# analog.net
KiCad netlist of a schematic drawn in Altium Designer
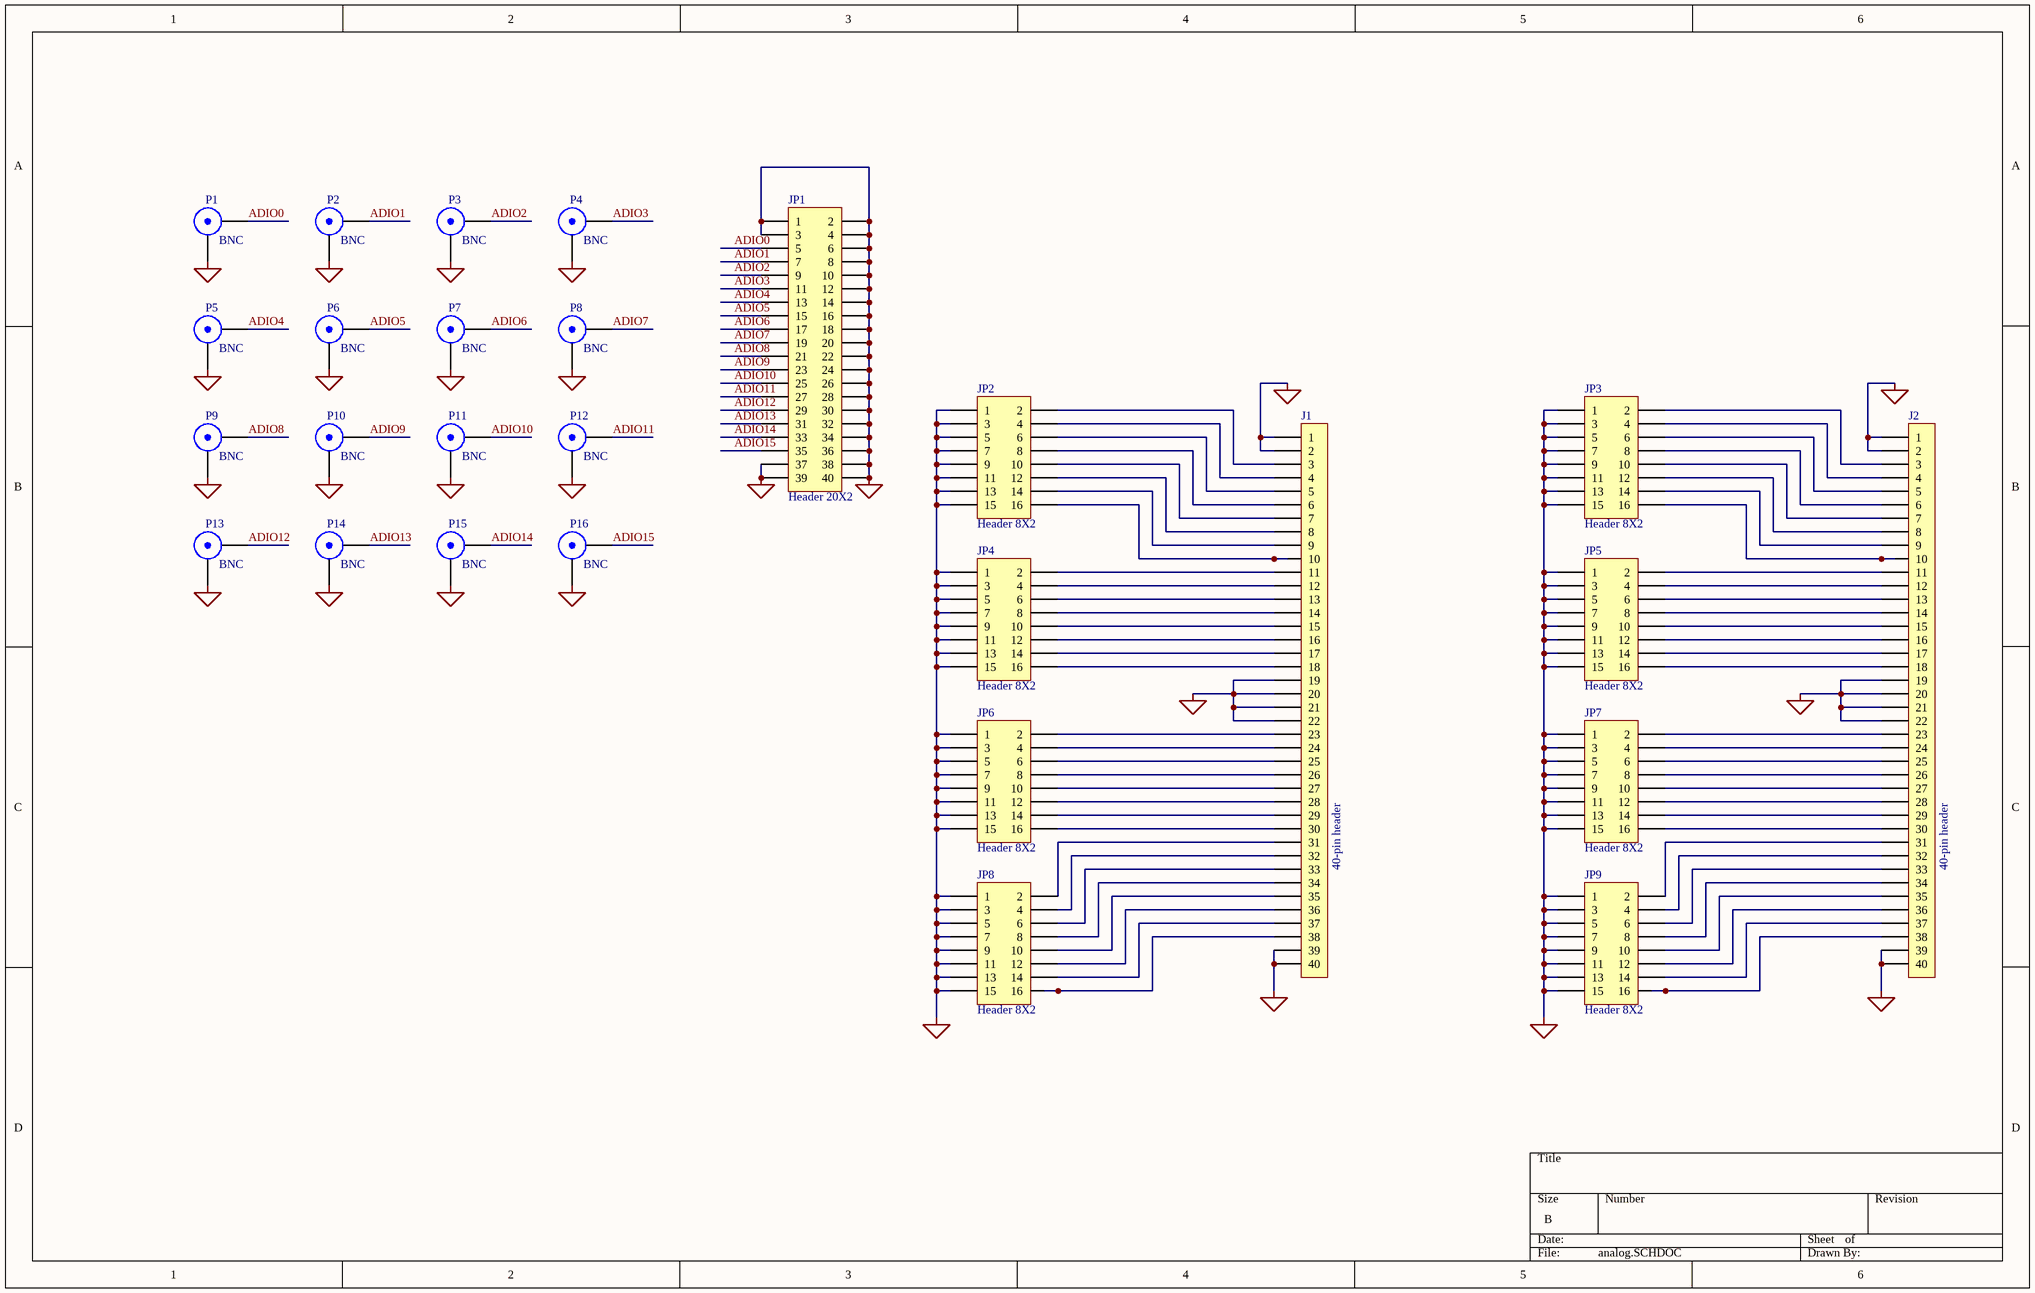
[diagram p0: analog.SCHDOC]

(export (version "E")
  (design (tool "Eeschema 10.0.6"))
  (components
    (comp (ref "J1")
      (value "40-pin header")
      (footprint "HDR2X20")
      (description "Simple 40pin connector")
      (libsource (lib "My devices") (part "40PINHEADER"))
    )
    (comp (ref "J2")
      (value "40-pin header")
      (footprint "HDR2X20")
      (description "Simple 40pin connector")
      (libsource (lib "My devices") (part "40PINHEADER"))
    )
    (comp (ref "JP1")
      (value "Header 20X2")
      (footprint "HDR2X20")
      (description "Header, 20-Pin, Dual row")
      (fields (field (name "MANUFACTURER") "Generic Components") (field (name "PUBLISHER") "Altium Limited"))
      (libsource (lib "Miscellaneous Connectors") (part "Header 20X2"))
    )
    (comp (ref "JP2")
      (value "Header 8X2")
      (footprint "HDR2X8")
      (description "Header, 8-Pin, Dual row")
      (fields (field (name "MANUFACTURER") "Generic Components") (field (name "PUBLISHER") "Altium Limited"))
      (libsource (lib "Miscellaneous Connectors") (part "Header 8X2"))
    )
    (comp (ref "JP3")
      (value "Header 8X2")
      (footprint "HDR2X8")
      (description "Header, 8-Pin, Dual row")
      (fields (field (name "MANUFACTURER") "Generic Components") (field (name "PUBLISHER") "Altium Limited"))
      (libsource (lib "Miscellaneous Connectors") (part "Header 8X2"))
    )
    (comp (ref "JP4")
      (value "Header 8X2")
      (footprint "HDR2X8")
      (description "Header, 8-Pin, Dual row")
      (fields (field (name "MANUFACTURER") "Generic Components") (field (name "PUBLISHER") "Altium Limited"))
      (libsource (lib "Miscellaneous Connectors") (part "Header 8X2"))
    )
    (comp (ref "JP5")
      (value "Header 8X2")
      (footprint "HDR2X8")
      (description "Header, 8-Pin, Dual row")
      (fields (field (name "MANUFACTURER") "Generic Components") (field (name "PUBLISHER") "Altium Limited"))
      (libsource (lib "Miscellaneous Connectors") (part "Header 8X2"))
    )
    (comp (ref "JP6")
      (value "Header 8X2")
      (footprint "HDR2X8")
      (description "Header, 8-Pin, Dual row")
      (fields (field (name "MANUFACTURER") "Generic Components") (field (name "PUBLISHER") "Altium Limited"))
      (libsource (lib "Miscellaneous Connectors") (part "Header 8X2"))
    )
    (comp (ref "JP7")
      (value "Header 8X2")
      (footprint "HDR2X8")
      (description "Header, 8-Pin, Dual row")
      (fields (field (name "MANUFACTURER") "Generic Components") (field (name "PUBLISHER") "Altium Limited"))
      (libsource (lib "Miscellaneous Connectors") (part "Header 8X2"))
    )
    (comp (ref "JP8")
      (value "Header 8X2")
      (footprint "HDR2X8")
      (description "Header, 8-Pin, Dual row")
      (fields (field (name "MANUFACTURER") "Generic Components") (field (name "PUBLISHER") "Altium Limited"))
      (libsource (lib "Miscellaneous Connectors") (part "Header 8X2"))
    )
    (comp (ref "JP9")
      (value "Header 8X2")
      (footprint "HDR2X8")
      (description "Header, 8-Pin, Dual row")
      (fields (field (name "MANUFACTURER") "Generic Components") (field (name "PUBLISHER") "Altium Limited"))
      (libsource (lib "Miscellaneous Connectors") (part "Header 8X2"))
    )
    (comp (ref "P1")
      (value "BNC")
      (footprint "Vertical BNC 227699-1")
      (description "BNC Elbow Connector")
      (fields (field (name "MANUFACTURER") "Generic Components") (field (name "PUBLISHER") "Altium Limited"))
      (libsource (lib "Miscellaneous Connectors") (part "BNC"))
    )
    (comp (ref "P2")
      (value "BNC")
      (footprint "Vertical BNC 227699-1")
      (description "BNC Elbow Connector")
      (fields (field (name "MANUFACTURER") "Generic Components") (field (name "PUBLISHER") "Altium Limited"))
      (libsource (lib "Miscellaneous Connectors") (part "BNC"))
    )
    (comp (ref "P3")
      (value "BNC")
      (footprint "Vertical BNC 227699-1")
      (description "BNC Elbow Connector")
      (fields (field (name "MANUFACTURER") "Generic Components") (field (name "PUBLISHER") "Altium Limited"))
      (libsource (lib "Miscellaneous Connectors") (part "BNC"))
    )
    (comp (ref "P4")
      (value "BNC")
      (footprint "Vertical BNC 227699-1")
      (description "BNC Elbow Connector")
      (fields (field (name "MANUFACTURER") "Generic Components") (field (name "PUBLISHER") "Altium Limited"))
      (libsource (lib "Miscellaneous Connectors") (part "BNC"))
    )
    (comp (ref "P5")
      (value "BNC")
      (footprint "Vertical BNC 227699-1")
      (description "BNC Elbow Connector")
      (fields (field (name "MANUFACTURER") "Generic Components") (field (name "PUBLISHER") "Altium Limited"))
      (libsource (lib "Miscellaneous Connectors") (part "BNC"))
    )
    (comp (ref "P6")
      (value "BNC")
      (footprint "Vertical BNC 227699-1")
      (description "BNC Elbow Connector")
      (fields (field (name "MANUFACTURER") "Generic Components") (field (name "PUBLISHER") "Altium Limited"))
      (libsource (lib "Miscellaneous Connectors") (part "BNC"))
    )
    (comp (ref "P7")
      (value "BNC")
      (footprint "Vertical BNC 227699-1")
      (description "BNC Elbow Connector")
      (fields (field (name "MANUFACTURER") "Generic Components") (field (name "PUBLISHER") "Altium Limited"))
      (libsource (lib "Miscellaneous Connectors") (part "BNC"))
    )
    (comp (ref "P8")
      (value "BNC")
      (footprint "Vertical BNC 227699-1")
      (description "BNC Elbow Connector")
      (fields (field (name "MANUFACTURER") "Generic Components") (field (name "PUBLISHER") "Altium Limited"))
      (libsource (lib "Miscellaneous Connectors") (part "BNC"))
    )
    (comp (ref "P9")
      (value "BNC")
      (footprint "Vertical BNC 227699-1")
      (description "BNC Elbow Connector")
      (fields (field (name "MANUFACTURER") "Generic Components") (field (name "PUBLISHER") "Altium Limited"))
      (libsource (lib "Miscellaneous Connectors") (part "BNC"))
    )
    (comp (ref "P10")
      (value "BNC")
      (footprint "Vertical BNC 227699-1")
      (description "BNC Elbow Connector")
      (fields (field (name "MANUFACTURER") "Generic Components") (field (name "PUBLISHER") "Altium Limited"))
      (libsource (lib "Miscellaneous Connectors") (part "BNC"))
    )
    (comp (ref "P11")
      (value "BNC")
      (footprint "Vertical BNC 227699-1")
      (description "BNC Elbow Connector")
      (fields (field (name "MANUFACTURER") "Generic Components") (field (name "PUBLISHER") "Altium Limited"))
      (libsource (lib "Miscellaneous Connectors") (part "BNC"))
    )
    (comp (ref "P12")
      (value "BNC")
      (footprint "Vertical BNC 227699-1")
      (description "BNC Elbow Connector")
      (fields (field (name "MANUFACTURER") "Generic Components") (field (name "PUBLISHER") "Altium Limited"))
      (libsource (lib "Miscellaneous Connectors") (part "BNC"))
    )
    (comp (ref "P13")
      (value "BNC")
      (footprint "Vertical BNC 227699-1")
      (description "BNC Elbow Connector")
      (fields (field (name "MANUFACTURER") "Generic Components") (field (name "PUBLISHER") "Altium Limited"))
      (libsource (lib "Miscellaneous Connectors") (part "BNC"))
    )
    (comp (ref "P14")
      (value "BNC")
      (footprint "Vertical BNC 227699-1")
      (description "BNC Elbow Connector")
      (fields (field (name "MANUFACTURER") "Generic Components") (field (name "PUBLISHER") "Altium Limited"))
      (libsource (lib "Miscellaneous Connectors") (part "BNC"))
    )
    (comp (ref "P15")
      (value "BNC")
      (footprint "Vertical BNC 227699-1")
      (description "BNC Elbow Connector")
      (fields (field (name "MANUFACTURER") "Generic Components") (field (name "PUBLISHER") "Altium Limited"))
      (libsource (lib "Miscellaneous Connectors") (part "BNC"))
    )
    (comp (ref "P16")
      (value "BNC")
      (footprint "Vertical BNC 227699-1")
      (description "BNC Elbow Connector")
      (fields (field (name "MANUFACTURER") "Generic Components") (field (name "PUBLISHER") "Altium Limited"))
      (libsource (lib "Miscellaneous Connectors") (part "BNC"))
    )
  )
  (nets
    (net (code "1") (name "/ADIO0") (class "Default")
      (node (ref "JP1") (pin "5") (pinfunction "5_5") (pintype "passive"))
      (node (ref "P1") (pin "1") (pinfunction "X_1") (pintype "passive"))
    )
    (net (code "2") (name "/ADIO1") (class "Default")
      (node (ref "JP1") (pin "7") (pinfunction "7_7") (pintype "passive"))
      (node (ref "P2") (pin "1") (pinfunction "X_1") (pintype "passive"))
    )
    (net (code "3") (name "/ADIO2") (class "Default")
      (node (ref "JP1") (pin "9") (pinfunction "9_9") (pintype "passive"))
      (node (ref "P3") (pin "1") (pinfunction "X_1") (pintype "passive"))
    )
    (net (code "4") (name "/ADIO3") (class "Default")
      (node (ref "JP1") (pin "11") (pinfunction "11_11") (pintype "passive"))
      (node (ref "P4") (pin "1") (pinfunction "X_1") (pintype "passive"))
    )
    (net (code "5") (name "/ADIO4") (class "Default")
      (node (ref "JP1") (pin "13") (pinfunction "13_13") (pintype "passive"))
      (node (ref "P5") (pin "1") (pinfunction "X_1") (pintype "passive"))
    )
    (net (code "6") (name "/ADIO5") (class "Default")
      (node (ref "JP1") (pin "15") (pinfunction "15_15") (pintype "passive"))
      (node (ref "P6") (pin "1") (pinfunction "X_1") (pintype "passive"))
    )
    (net (code "7") (name "/ADIO6") (class "Default")
      (node (ref "JP1") (pin "17") (pinfunction "17_17") (pintype "passive"))
      (node (ref "P7") (pin "1") (pinfunction "X_1") (pintype "passive"))
    )
    (net (code "8") (name "/ADIO7") (class "Default")
      (node (ref "JP1") (pin "19") (pinfunction "19_19") (pintype "passive"))
      (node (ref "P8") (pin "1") (pinfunction "X_1") (pintype "passive"))
    )
    (net (code "9") (name "/ADIO8") (class "Default")
      (node (ref "JP1") (pin "21") (pinfunction "21_21") (pintype "passive"))
      (node (ref "P9") (pin "1") (pinfunction "X_1") (pintype "passive"))
    )
    (net (code "10") (name "/ADIO9") (class "Default")
      (node (ref "JP1") (pin "23") (pinfunction "23_23") (pintype "passive"))
      (node (ref "P10") (pin "1") (pinfunction "X_1") (pintype "passive"))
    )
    (net (code "11") (name "/ADIO10") (class "Default")
      (node (ref "JP1") (pin "25") (pinfunction "25_25") (pintype "passive"))
      (node (ref "P11") (pin "1") (pinfunction "X_1") (pintype "passive"))
    )
    (net (code "12") (name "/ADIO11") (class "Default")
      (node (ref "JP1") (pin "27") (pinfunction "27_27") (pintype "passive"))
      (node (ref "P12") (pin "1") (pinfunction "X_1") (pintype "passive"))
    )
    (net (code "13") (name "/ADIO12") (class "Default")
      (node (ref "JP1") (pin "29") (pinfunction "29_29") (pintype "passive"))
      (node (ref "P13") (pin "1") (pinfunction "X_1") (pintype "passive"))
    )
    (net (code "14") (name "/ADIO13") (class "Default")
      (node (ref "JP1") (pin "31") (pinfunction "31_31") (pintype "passive"))
      (node (ref "P14") (pin "1") (pinfunction "X_1") (pintype "passive"))
    )
    (net (code "15") (name "/ADIO14") (class "Default")
      (node (ref "JP1") (pin "33") (pinfunction "33_33") (pintype "passive"))
      (node (ref "P15") (pin "1") (pinfunction "X_1") (pintype "passive"))
    )
    (net (code "16") (name "/ADIO15") (class "Default")
      (node (ref "JP1") (pin "35") (pinfunction "35_35") (pintype "passive"))
      (node (ref "P16") (pin "1") (pinfunction "X_1") (pintype "passive"))
    )
    (net (code "17") (name "AGND") (class "Default")
      (node (ref "JP1") (pin "1") (pinfunction "1_1") (pintype "passive"))
      (node (ref "JP1") (pin "10") (pinfunction "10_10") (pintype "passive"))
      (node (ref "JP1") (pin "12") (pinfunction "12_12") (pintype "passive"))
      (node (ref "JP1") (pin "14") (pinfunction "14_14") (pintype "passive"))
      (node (ref "JP1") (pin "16") (pinfunction "16_16") (pintype "passive"))
      (node (ref "JP1") (pin "18") (pinfunction "18_18") (pintype "passive"))
      (node (ref "JP1") (pin "2") (pinfunction "2_2") (pintype "passive"))
      (node (ref "JP1") (pin "20") (pinfunction "20_20") (pintype "passive"))
      (node (ref "JP1") (pin "22") (pinfunction "22_22") (pintype "passive"))
      (node (ref "JP1") (pin "24") (pinfunction "24_24") (pintype "passive"))
      (node (ref "JP1") (pin "26") (pinfunction "26_26") (pintype "passive"))
      (node (ref "JP1") (pin "28") (pinfunction "28_28") (pintype "passive"))
      (node (ref "JP1") (pin "3") (pinfunction "3_3") (pintype "passive"))
      (node (ref "JP1") (pin "30") (pinfunction "30_30") (pintype "passive"))
      (node (ref "JP1") (pin "32") (pinfunction "32_32") (pintype "passive"))
      (node (ref "JP1") (pin "34") (pinfunction "34_34") (pintype "passive"))
      (node (ref "JP1") (pin "36") (pinfunction "36_36") (pintype "passive"))
      (node (ref "JP1") (pin "37") (pinfunction "37_37") (pintype "passive"))
      (node (ref "JP1") (pin "38") (pinfunction "38_38") (pintype "passive"))
      (node (ref "JP1") (pin "39") (pinfunction "39_39") (pintype "passive"))
      (node (ref "JP1") (pin "4") (pinfunction "4_4") (pintype "passive"))
      (node (ref "JP1") (pin "40") (pinfunction "40_40") (pintype "passive"))
      (node (ref "JP1") (pin "6") (pinfunction "6_6") (pintype "passive"))
      (node (ref "JP1") (pin "8") (pinfunction "8_8") (pintype "passive"))
      (node (ref "P1") (pin "2") (pinfunction "Y_2") (pintype "passive"))
      (node (ref "P10") (pin "2") (pinfunction "Y_2") (pintype "passive"))
      (node (ref "P11") (pin "2") (pinfunction "Y_2") (pintype "passive"))
      (node (ref "P12") (pin "2") (pinfunction "Y_2") (pintype "passive"))
      (node (ref "P13") (pin "2") (pinfunction "Y_2") (pintype "passive"))
      (node (ref "P14") (pin "2") (pinfunction "Y_2") (pintype "passive"))
      (node (ref "P15") (pin "2") (pinfunction "Y_2") (pintype "passive"))
      (node (ref "P16") (pin "2") (pinfunction "Y_2") (pintype "passive"))
      (node (ref "P2") (pin "2") (pinfunction "Y_2") (pintype "passive"))
      (node (ref "P3") (pin "2") (pinfunction "Y_2") (pintype "passive"))
      (node (ref "P4") (pin "2") (pinfunction "Y_2") (pintype "passive"))
      (node (ref "P5") (pin "2") (pinfunction "Y_2") (pintype "passive"))
      (node (ref "P6") (pin "2") (pinfunction "Y_2") (pintype "passive"))
      (node (ref "P7") (pin "2") (pinfunction "Y_2") (pintype "passive"))
      (node (ref "P8") (pin "2") (pinfunction "Y_2") (pintype "passive"))
      (node (ref "P9") (pin "2") (pinfunction "Y_2") (pintype "passive"))
    )
    (net (code "18") (name "DGND") (class "Default")
      (node (ref "J1") (pin "1") (pinfunction "1_1") (pintype "passive"))
      (node (ref "J1") (pin "19") (pinfunction "19_19") (pintype "passive"))
      (node (ref "J1") (pin "2") (pinfunction "2_2") (pintype "passive"))
      (node (ref "J1") (pin "20") (pinfunction "20_20") (pintype "passive"))
      (node (ref "J1") (pin "21") (pinfunction "21_21") (pintype "passive"))
      (node (ref "J1") (pin "22") (pinfunction "22_22") (pintype "passive"))
      (node (ref "J1") (pin "39") (pinfunction "39_39") (pintype "passive"))
      (node (ref "J1") (pin "40") (pinfunction "40_40") (pintype "passive"))
      (node (ref "J2") (pin "1") (pinfunction "1_1") (pintype "passive"))
      (node (ref "J2") (pin "19") (pinfunction "19_19") (pintype "passive"))
      (node (ref "J2") (pin "2") (pinfunction "2_2") (pintype "passive"))
      (node (ref "J2") (pin "20") (pinfunction "20_20") (pintype "passive"))
      (node (ref "J2") (pin "21") (pinfunction "21_21") (pintype "passive"))
      (node (ref "J2") (pin "22") (pinfunction "22_22") (pintype "passive"))
      (node (ref "J2") (pin "39") (pinfunction "39_39") (pintype "passive"))
      (node (ref "J2") (pin "40") (pinfunction "40_40") (pintype "passive"))
      (node (ref "JP2") (pin "1") (pinfunction "1_1") (pintype "passive"))
      (node (ref "JP2") (pin "11") (pinfunction "11_11") (pintype "passive"))
      (node (ref "JP2") (pin "13") (pinfunction "13_13") (pintype "passive"))
      (node (ref "JP2") (pin "15") (pinfunction "15_15") (pintype "passive"))
      (node (ref "JP2") (pin "3") (pinfunction "3_3") (pintype "passive"))
      (node (ref "JP2") (pin "5") (pinfunction "5_5") (pintype "passive"))
      (node (ref "JP2") (pin "7") (pinfunction "7_7") (pintype "passive"))
      (node (ref "JP2") (pin "9") (pinfunction "9_9") (pintype "passive"))
      (node (ref "JP3") (pin "1") (pinfunction "1_1") (pintype "passive"))
      (node (ref "JP3") (pin "11") (pinfunction "11_11") (pintype "passive"))
      (node (ref "JP3") (pin "13") (pinfunction "13_13") (pintype "passive"))
      (node (ref "JP3") (pin "15") (pinfunction "15_15") (pintype "passive"))
      (node (ref "JP3") (pin "3") (pinfunction "3_3") (pintype "passive"))
      (node (ref "JP3") (pin "5") (pinfunction "5_5") (pintype "passive"))
      (node (ref "JP3") (pin "7") (pinfunction "7_7") (pintype "passive"))
      (node (ref "JP3") (pin "9") (pinfunction "9_9") (pintype "passive"))
      (node (ref "JP4") (pin "1") (pinfunction "1_1") (pintype "passive"))
      (node (ref "JP4") (pin "11") (pinfunction "11_11") (pintype "passive"))
      (node (ref "JP4") (pin "13") (pinfunction "13_13") (pintype "passive"))
      (node (ref "JP4") (pin "15") (pinfunction "15_15") (pintype "passive"))
      (node (ref "JP4") (pin "3") (pinfunction "3_3") (pintype "passive"))
      (node (ref "JP4") (pin "5") (pinfunction "5_5") (pintype "passive"))
      (node (ref "JP4") (pin "7") (pinfunction "7_7") (pintype "passive"))
      (node (ref "JP4") (pin "9") (pinfunction "9_9") (pintype "passive"))
      (node (ref "JP5") (pin "1") (pinfunction "1_1") (pintype "passive"))
      (node (ref "JP5") (pin "11") (pinfunction "11_11") (pintype "passive"))
      (node (ref "JP5") (pin "13") (pinfunction "13_13") (pintype "passive"))
      (node (ref "JP5") (pin "15") (pinfunction "15_15") (pintype "passive"))
      (node (ref "JP5") (pin "3") (pinfunction "3_3") (pintype "passive"))
      (node (ref "JP5") (pin "5") (pinfunction "5_5") (pintype "passive"))
      (node (ref "JP5") (pin "7") (pinfunction "7_7") (pintype "passive"))
      (node (ref "JP5") (pin "9") (pinfunction "9_9") (pintype "passive"))
      (node (ref "JP6") (pin "1") (pinfunction "1_1") (pintype "passive"))
      (node (ref "JP6") (pin "11") (pinfunction "11_11") (pintype "passive"))
      (node (ref "JP6") (pin "13") (pinfunction "13_13") (pintype "passive"))
      (node (ref "JP6") (pin "15") (pinfunction "15_15") (pintype "passive"))
      (node (ref "JP6") (pin "3") (pinfunction "3_3") (pintype "passive"))
      (node (ref "JP6") (pin "5") (pinfunction "5_5") (pintype "passive"))
      (node (ref "JP6") (pin "7") (pinfunction "7_7") (pintype "passive"))
      (node (ref "JP6") (pin "9") (pinfunction "9_9") (pintype "passive"))
      (node (ref "JP7") (pin "1") (pinfunction "1_1") (pintype "passive"))
      (node (ref "JP7") (pin "11") (pinfunction "11_11") (pintype "passive"))
      (node (ref "JP7") (pin "13") (pinfunction "13_13") (pintype "passive"))
      (node (ref "JP7") (pin "15") (pinfunction "15_15") (pintype "passive"))
      (node (ref "JP7") (pin "3") (pinfunction "3_3") (pintype "passive"))
      (node (ref "JP7") (pin "5") (pinfunction "5_5") (pintype "passive"))
      (node (ref "JP7") (pin "7") (pinfunction "7_7") (pintype "passive"))
      (node (ref "JP7") (pin "9") (pinfunction "9_9") (pintype "passive"))
      (node (ref "JP8") (pin "1") (pinfunction "1_1") (pintype "passive"))
      (node (ref "JP8") (pin "11") (pinfunction "11_11") (pintype "passive"))
      (node (ref "JP8") (pin "13") (pinfunction "13_13") (pintype "passive"))
      (node (ref "JP8") (pin "15") (pinfunction "15_15") (pintype "passive"))
      (node (ref "JP8") (pin "3") (pinfunction "3_3") (pintype "passive"))
      (node (ref "JP8") (pin "5") (pinfunction "5_5") (pintype "passive"))
      (node (ref "JP8") (pin "7") (pinfunction "7_7") (pintype "passive"))
      (node (ref "JP8") (pin "9") (pinfunction "9_9") (pintype "passive"))
      (node (ref "JP9") (pin "1") (pinfunction "1_1") (pintype "passive"))
      (node (ref "JP9") (pin "11") (pinfunction "11_11") (pintype "passive"))
      (node (ref "JP9") (pin "13") (pinfunction "13_13") (pintype "passive"))
      (node (ref "JP9") (pin "15") (pinfunction "15_15") (pintype "passive"))
      (node (ref "JP9") (pin "3") (pinfunction "3_3") (pintype "passive"))
      (node (ref "JP9") (pin "5") (pinfunction "5_5") (pintype "passive"))
      (node (ref "JP9") (pin "7") (pinfunction "7_7") (pintype "passive"))
      (node (ref "JP9") (pin "9") (pinfunction "9_9") (pintype "passive"))
    )
    (net (code "19") (name "Net-(J1-Pad3)") (class "Default")
      (node (ref "J1") (pin "3") (pinfunction "3_3") (pintype "passive"))
      (node (ref "JP2") (pin "2") (pinfunction "2_2") (pintype "passive"))
    )
    (net (code "20") (name "Net-(J1-Pad4)") (class "Default")
      (node (ref "J1") (pin "4") (pinfunction "4_4") (pintype "passive"))
      (node (ref "JP2") (pin "4") (pinfunction "4_4") (pintype "passive"))
    )
    (net (code "21") (name "Net-(J1-Pad5)") (class "Default")
      (node (ref "J1") (pin "5") (pinfunction "5_5") (pintype "passive"))
      (node (ref "JP2") (pin "6") (pinfunction "6_6") (pintype "passive"))
    )
    (net (code "22") (name "Net-(J1-Pad6)") (class "Default")
      (node (ref "J1") (pin "6") (pinfunction "6_6") (pintype "passive"))
      (node (ref "JP2") (pin "8") (pinfunction "8_8") (pintype "passive"))
    )
    (net (code "23") (name "Net-(J1-Pad7)") (class "Default")
      (node (ref "J1") (pin "7") (pinfunction "7_7") (pintype "passive"))
      (node (ref "JP2") (pin "10") (pinfunction "10_10") (pintype "passive"))
    )
    (net (code "24") (name "Net-(J1-Pad8)") (class "Default")
      (node (ref "J1") (pin "8") (pinfunction "8_8") (pintype "passive"))
      (node (ref "JP2") (pin "12") (pinfunction "12_12") (pintype "passive"))
    )
    (net (code "25") (name "Net-(J1-Pad9)") (class "Default")
      (node (ref "J1") (pin "9") (pinfunction "9_9") (pintype "passive"))
      (node (ref "JP2") (pin "14") (pinfunction "14_14") (pintype "passive"))
    )
    (net (code "26") (name "Net-(J1-Pad10)") (class "Default")
      (node (ref "J1") (pin "10") (pinfunction "10_10") (pintype "passive"))
      (node (ref "JP2") (pin "16") (pinfunction "16_16") (pintype "passive"))
    )
    (net (code "27") (name "Net-(J1-Pad11)") (class "Default")
      (node (ref "J1") (pin "11") (pinfunction "11_11") (pintype "passive"))
      (node (ref "JP4") (pin "2") (pinfunction "2_2") (pintype "passive"))
    )
    (net (code "28") (name "Net-(J1-Pad12)") (class "Default")
      (node (ref "J1") (pin "12") (pinfunction "12_12") (pintype "passive"))
      (node (ref "JP4") (pin "4") (pinfunction "4_4") (pintype "passive"))
    )
    (net (code "29") (name "Net-(J1-Pad13)") (class "Default")
      (node (ref "J1") (pin "13") (pinfunction "13_13") (pintype "passive"))
      (node (ref "JP4") (pin "6") (pinfunction "6_6") (pintype "passive"))
    )
    (net (code "30") (name "Net-(J1-Pad14)") (class "Default")
      (node (ref "J1") (pin "14") (pinfunction "14_14") (pintype "passive"))
      (node (ref "JP4") (pin "8") (pinfunction "8_8") (pintype "passive"))
    )
    (net (code "31") (name "Net-(J1-Pad15)") (class "Default")
      (node (ref "J1") (pin "15") (pinfunction "15_15") (pintype "passive"))
      (node (ref "JP4") (pin "10") (pinfunction "10_10") (pintype "passive"))
    )
    (net (code "32") (name "Net-(J1-Pad16)") (class "Default")
      (node (ref "J1") (pin "16") (pinfunction "16_16") (pintype "passive"))
      (node (ref "JP4") (pin "12") (pinfunction "12_12") (pintype "passive"))
    )
    (net (code "33") (name "Net-(J1-Pad17)") (class "Default")
      (node (ref "J1") (pin "17") (pinfunction "17_17") (pintype "passive"))
      (node (ref "JP4") (pin "14") (pinfunction "14_14") (pintype "passive"))
    )
    (net (code "34") (name "Net-(J1-Pad18)") (class "Default")
      (node (ref "J1") (pin "18") (pinfunction "18_18") (pintype "passive"))
      (node (ref "JP4") (pin "16") (pinfunction "16_16") (pintype "passive"))
    )
    (net (code "35") (name "Net-(J1-Pad23)") (class "Default")
      (node (ref "J1") (pin "23") (pinfunction "23_23") (pintype "passive"))
      (node (ref "JP6") (pin "2") (pinfunction "2_2") (pintype "passive"))
    )
    (net (code "36") (name "Net-(J1-Pad24)") (class "Default")
      (node (ref "J1") (pin "24") (pinfunction "24_24") (pintype "passive"))
      (node (ref "JP6") (pin "4") (pinfunction "4_4") (pintype "passive"))
    )
    (net (code "37") (name "Net-(J1-Pad25)") (class "Default")
      (node (ref "J1") (pin "25") (pinfunction "25_25") (pintype "passive"))
      (node (ref "JP6") (pin "6") (pinfunction "6_6") (pintype "passive"))
    )
    (net (code "38") (name "Net-(J1-Pad26)") (class "Default")
      (node (ref "J1") (pin "26") (pinfunction "26_26") (pintype "passive"))
      (node (ref "JP6") (pin "8") (pinfunction "8_8") (pintype "passive"))
    )
    (net (code "39") (name "Net-(J1-Pad27)") (class "Default")
      (node (ref "J1") (pin "27") (pinfunction "27_27") (pintype "passive"))
      (node (ref "JP6") (pin "10") (pinfunction "10_10") (pintype "passive"))
    )
    (net (code "40") (name "Net-(J1-Pad28)") (class "Default")
      (node (ref "J1") (pin "28") (pinfunction "28_28") (pintype "passive"))
      (node (ref "JP6") (pin "12") (pinfunction "12_12") (pintype "passive"))
    )
    (net (code "41") (name "Net-(J1-Pad29)") (class "Default")
      (node (ref "J1") (pin "29") (pinfunction "29_29") (pintype "passive"))
      (node (ref "JP6") (pin "14") (pinfunction "14_14") (pintype "passive"))
    )
    (net (code "42") (name "Net-(J1-Pad30)") (class "Default")
      (node (ref "J1") (pin "30") (pinfunction "30_30") (pintype "passive"))
      (node (ref "JP6") (pin "16") (pinfunction "16_16") (pintype "passive"))
    )
    (net (code "43") (name "Net-(J1-Pad31)") (class "Default")
      (node (ref "J1") (pin "31") (pinfunction "31_31") (pintype "passive"))
      (node (ref "JP8") (pin "2") (pinfunction "2_2") (pintype "passive"))
    )
    (net (code "44") (name "Net-(J1-Pad32)") (class "Default")
      (node (ref "J1") (pin "32") (pinfunction "32_32") (pintype "passive"))
      (node (ref "JP8") (pin "4") (pinfunction "4_4") (pintype "passive"))
    )
    (net (code "45") (name "Net-(J1-Pad33)") (class "Default")
      (node (ref "J1") (pin "33") (pinfunction "33_33") (pintype "passive"))
      (node (ref "JP8") (pin "6") (pinfunction "6_6") (pintype "passive"))
    )
    (net (code "46") (name "Net-(J1-Pad34)") (class "Default")
      (node (ref "J1") (pin "34") (pinfunction "34_34") (pintype "passive"))
      (node (ref "JP8") (pin "8") (pinfunction "8_8") (pintype "passive"))
    )
    (net (code "47") (name "Net-(J1-Pad35)") (class "Default")
      (node (ref "J1") (pin "35") (pinfunction "35_35") (pintype "passive"))
      (node (ref "JP8") (pin "10") (pinfunction "10_10") (pintype "passive"))
    )
    (net (code "48") (name "Net-(J1-Pad36)") (class "Default")
      (node (ref "J1") (pin "36") (pinfunction "36_36") (pintype "passive"))
      (node (ref "JP8") (pin "12") (pinfunction "12_12") (pintype "passive"))
    )
    (net (code "49") (name "Net-(J1-Pad37)") (class "Default")
      (node (ref "J1") (pin "37") (pinfunction "37_37") (pintype "passive"))
      (node (ref "JP8") (pin "14") (pinfunction "14_14") (pintype "passive"))
    )
    (net (code "50") (name "Net-(J1-Pad38)") (class "Default")
      (node (ref "J1") (pin "38") (pinfunction "38_38") (pintype "passive"))
      (node (ref "JP8") (pin "16") (pinfunction "16_16") (pintype "passive"))
    )
    (net (code "51") (name "Net-(J2-Pad3)") (class "Default")
      (node (ref "J2") (pin "3") (pinfunction "3_3") (pintype "passive"))
      (node (ref "JP3") (pin "2") (pinfunction "2_2") (pintype "passive"))
    )
    (net (code "52") (name "Net-(J2-Pad4)") (class "Default")
      (node (ref "J2") (pin "4") (pinfunction "4_4") (pintype "passive"))
      (node (ref "JP3") (pin "4") (pinfunction "4_4") (pintype "passive"))
    )
    (net (code "53") (name "Net-(J2-Pad5)") (class "Default")
      (node (ref "J2") (pin "5") (pinfunction "5_5") (pintype "passive"))
      (node (ref "JP3") (pin "6") (pinfunction "6_6") (pintype "passive"))
    )
    (net (code "54") (name "Net-(J2-Pad6)") (class "Default")
      (node (ref "J2") (pin "6") (pinfunction "6_6") (pintype "passive"))
      (node (ref "JP3") (pin "8") (pinfunction "8_8") (pintype "passive"))
    )
    (net (code "55") (name "Net-(J2-Pad7)") (class "Default")
      (node (ref "J2") (pin "7") (pinfunction "7_7") (pintype "passive"))
      (node (ref "JP3") (pin "10") (pinfunction "10_10") (pintype "passive"))
    )
    (net (code "56") (name "Net-(J2-Pad8)") (class "Default")
      (node (ref "J2") (pin "8") (pinfunction "8_8") (pintype "passive"))
      (node (ref "JP3") (pin "12") (pinfunction "12_12") (pintype "passive"))
    )
    (net (code "57") (name "Net-(J2-Pad9)") (class "Default")
      (node (ref "J2") (pin "9") (pinfunction "9_9") (pintype "passive"))
      (node (ref "JP3") (pin "14") (pinfunction "14_14") (pintype "passive"))
    )
    (net (code "58") (name "Net-(J2-Pad10)") (class "Default")
      (node (ref "J2") (pin "10") (pinfunction "10_10") (pintype "passive"))
      (node (ref "JP3") (pin "16") (pinfunction "16_16") (pintype "passive"))
    )
    (net (code "59") (name "Net-(J2-Pad11)") (class "Default")
      (node (ref "J2") (pin "11") (pinfunction "11_11") (pintype "passive"))
      (node (ref "JP5") (pin "2") (pinfunction "2_2") (pintype "passive"))
    )
    (net (code "60") (name "Net-(J2-Pad12)") (class "Default")
      (node (ref "J2") (pin "12") (pinfunction "12_12") (pintype "passive"))
      (node (ref "JP5") (pin "4") (pinfunction "4_4") (pintype "passive"))
    )
    (net (code "61") (name "Net-(J2-Pad13)") (class "Default")
      (node (ref "J2") (pin "13") (pinfunction "13_13") (pintype "passive"))
      (node (ref "JP5") (pin "6") (pinfunction "6_6") (pintype "passive"))
    )
    (net (code "62") (name "Net-(J2-Pad14)") (class "Default")
      (node (ref "J2") (pin "14") (pinfunction "14_14") (pintype "passive"))
      (node (ref "JP5") (pin "8") (pinfunction "8_8") (pintype "passive"))
    )
    (net (code "63") (name "Net-(J2-Pad15)") (class "Default")
      (node (ref "J2") (pin "15") (pinfunction "15_15") (pintype "passive"))
      (node (ref "JP5") (pin "10") (pinfunction "10_10") (pintype "passive"))
    )
    (net (code "64") (name "Net-(J2-Pad16)") (class "Default")
      (node (ref "J2") (pin "16") (pinfunction "16_16") (pintype "passive"))
      (node (ref "JP5") (pin "12") (pinfunction "12_12") (pintype "passive"))
    )
    (net (code "65") (name "Net-(J2-Pad17)") (class "Default")
      (node (ref "J2") (pin "17") (pinfunction "17_17") (pintype "passive"))
      (node (ref "JP5") (pin "14") (pinfunction "14_14") (pintype "passive"))
    )
    (net (code "66") (name "Net-(J2-Pad18)") (class "Default")
      (node (ref "J2") (pin "18") (pinfunction "18_18") (pintype "passive"))
      (node (ref "JP5") (pin "16") (pinfunction "16_16") (pintype "passive"))
    )
    (net (code "67") (name "Net-(J2-Pad23)") (class "Default")
      (node (ref "J2") (pin "23") (pinfunction "23_23") (pintype "passive"))
      (node (ref "JP7") (pin "2") (pinfunction "2_2") (pintype "passive"))
    )
    (net (code "68") (name "Net-(J2-Pad24)") (class "Default")
      (node (ref "J2") (pin "24") (pinfunction "24_24") (pintype "passive"))
      (node (ref "JP7") (pin "4") (pinfunction "4_4") (pintype "passive"))
    )
    (net (code "69") (name "Net-(J2-Pad25)") (class "Default")
      (node (ref "J2") (pin "25") (pinfunction "25_25") (pintype "passive"))
      (node (ref "JP7") (pin "6") (pinfunction "6_6") (pintype "passive"))
    )
    (net (code "70") (name "Net-(J2-Pad26)") (class "Default")
      (node (ref "J2") (pin "26") (pinfunction "26_26") (pintype "passive"))
      (node (ref "JP7") (pin "8") (pinfunction "8_8") (pintype "passive"))
    )
    (net (code "71") (name "Net-(J2-Pad27)") (class "Default")
      (node (ref "J2") (pin "27") (pinfunction "27_27") (pintype "passive"))
      (node (ref "JP7") (pin "10") (pinfunction "10_10") (pintype "passive"))
    )
    (net (code "72") (name "Net-(J2-Pad28)") (class "Default")
      (node (ref "J2") (pin "28") (pinfunction "28_28") (pintype "passive"))
      (node (ref "JP7") (pin "12") (pinfunction "12_12") (pintype "passive"))
    )
    (net (code "73") (name "Net-(J2-Pad29)") (class "Default")
      (node (ref "J2") (pin "29") (pinfunction "29_29") (pintype "passive"))
      (node (ref "JP7") (pin "14") (pinfunction "14_14") (pintype "passive"))
    )
    (net (code "74") (name "Net-(J2-Pad30)") (class "Default")
      (node (ref "J2") (pin "30") (pinfunction "30_30") (pintype "passive"))
      (node (ref "JP7") (pin "16") (pinfunction "16_16") (pintype "passive"))
    )
    (net (code "75") (name "Net-(J2-Pad31)") (class "Default")
      (node (ref "J2") (pin "31") (pinfunction "31_31") (pintype "passive"))
      (node (ref "JP9") (pin "2") (pinfunction "2_2") (pintype "passive"))
    )
    (net (code "76") (name "Net-(J2-Pad32)") (class "Default")
      (node (ref "J2") (pin "32") (pinfunction "32_32") (pintype "passive"))
      (node (ref "JP9") (pin "4") (pinfunction "4_4") (pintype "passive"))
    )
    (net (code "77") (name "Net-(J2-Pad33)") (class "Default")
      (node (ref "J2") (pin "33") (pinfunction "33_33") (pintype "passive"))
      (node (ref "JP9") (pin "6") (pinfunction "6_6") (pintype "passive"))
    )
    (net (code "78") (name "Net-(J2-Pad34)") (class "Default")
      (node (ref "J2") (pin "34") (pinfunction "34_34") (pintype "passive"))
      (node (ref "JP9") (pin "8") (pinfunction "8_8") (pintype "passive"))
    )
    (net (code "79") (name "Net-(J2-Pad35)") (class "Default")
      (node (ref "J2") (pin "35") (pinfunction "35_35") (pintype "passive"))
      (node (ref "JP9") (pin "10") (pinfunction "10_10") (pintype "passive"))
    )
    (net (code "80") (name "Net-(J2-Pad36)") (class "Default")
      (node (ref "J2") (pin "36") (pinfunction "36_36") (pintype "passive"))
      (node (ref "JP9") (pin "12") (pinfunction "12_12") (pintype "passive"))
    )
    (net (code "81") (name "Net-(J2-Pad37)") (class "Default")
      (node (ref "J2") (pin "37") (pinfunction "37_37") (pintype "passive"))
      (node (ref "JP9") (pin "14") (pinfunction "14_14") (pintype "passive"))
    )
    (net (code "82") (name "Net-(J2-Pad38)") (class "Default")
      (node (ref "J2") (pin "38") (pinfunction "38_38") (pintype "passive"))
      (node (ref "JP9") (pin "16") (pinfunction "16_16") (pintype "passive"))
    )
  )
)
